# motherboard.net
KiCad netlist of a schematic drawn in EAGLE
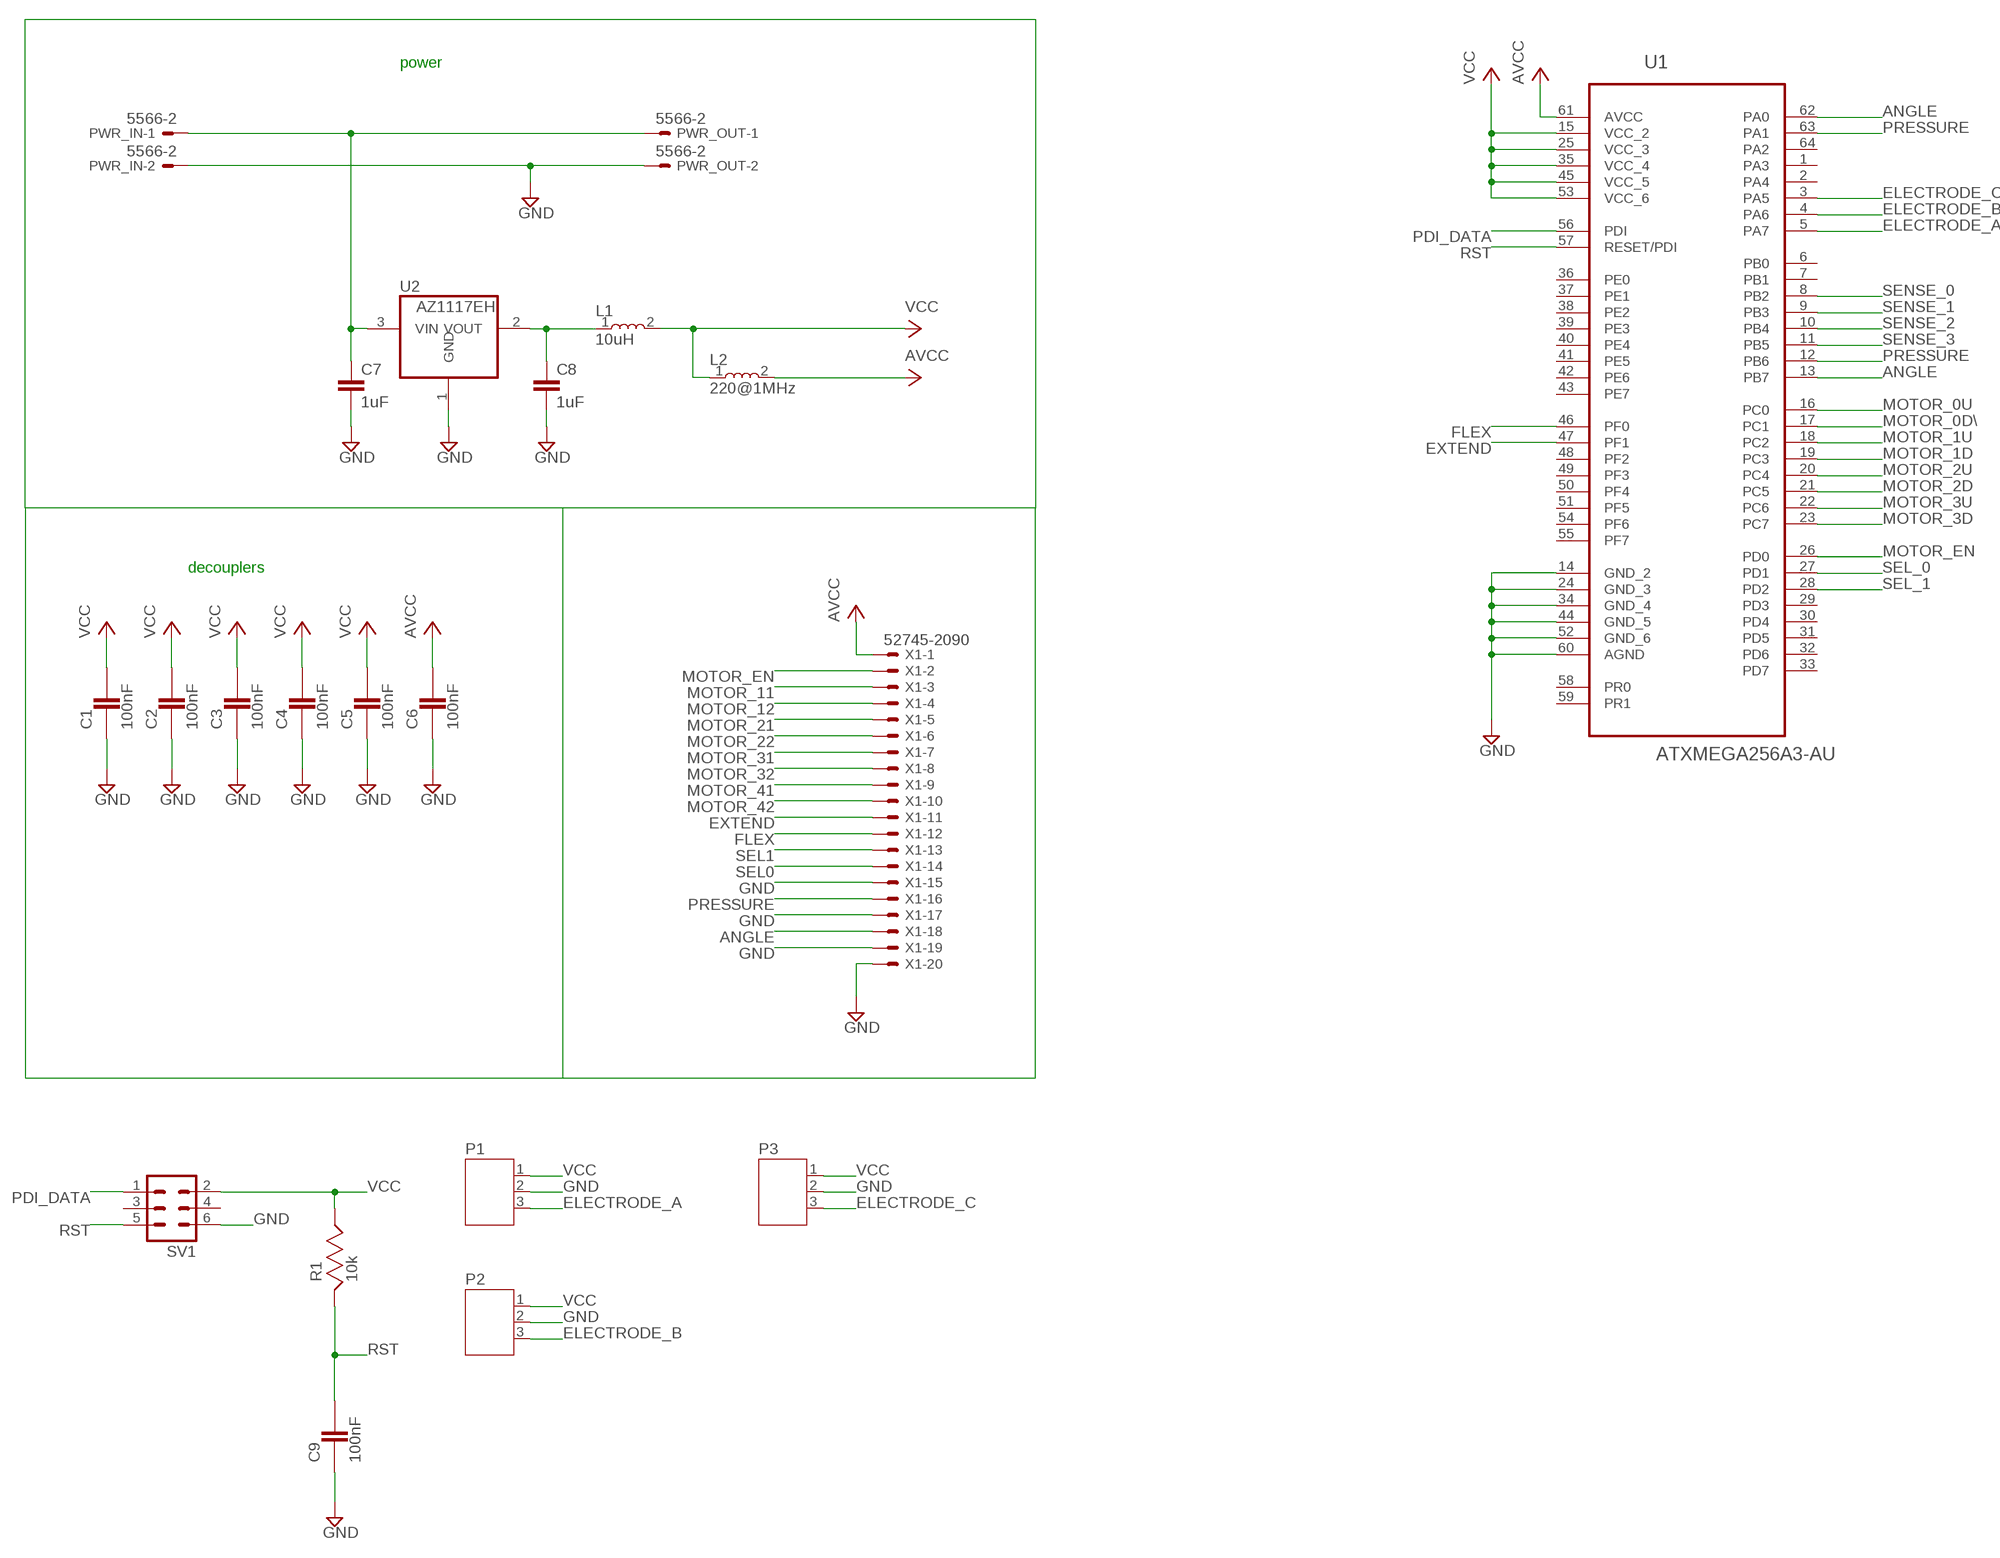
[diagram p0: schematic, sheet 1]

(export (version "E")
  (design (tool "Eeschema 10.0.6"))
  (components
    (comp (ref "C1")
      (value "100nF")
      (footprint "eagle-import:0508")
      (libsource (lib "eagle-import") (part "C0508"))
    )
    (comp (ref "C2")
      (value "100nF")
      (footprint "eagle-import:0508")
      (libsource (lib "eagle-import") (part "C0508"))
    )
    (comp (ref "C3")
      (value "100nF")
      (footprint "eagle-import:0508")
      (libsource (lib "eagle-import") (part "C0508"))
    )
    (comp (ref "C4")
      (value "100nF")
      (footprint "eagle-import:0508")
      (libsource (lib "eagle-import") (part "C0508"))
    )
    (comp (ref "C5")
      (value "100nF")
      (footprint "eagle-import:0508")
      (libsource (lib "eagle-import") (part "C0508"))
    )
    (comp (ref "C6")
      (value "100nF")
      (footprint "eagle-import:0508")
      (libsource (lib "eagle-import") (part "C0508"))
    )
    (comp (ref "C7")
      (value "1uF")
      (footprint "eagle-import:C0805")
      (libsource (lib "eagle-import") (part "C-EUC0805"))
    )
    (comp (ref "C8")
      (value "1uF")
      (footprint "eagle-import:C0805")
      (libsource (lib "eagle-import") (part "C-EUC0805"))
    )
    (comp (ref "C9")
      (value "100nF")
      (footprint "eagle-import:CC0603KRX7R8BB105_CAPC1608X90")
      (fields (field (name "MANUFACTURER") "YAGEO"))
      (libsource (lib "eagle-import") (part "CC0603KRX7R8BB105"))
    )
    (comp (ref "L1")
      (value "10uH")
      (footprint "eagle-import:0805")
      (libsource (lib "eagle-import") (part "L0805"))
    )
    (comp (ref "L2")
      (value "220@1MHz")
      (footprint "eagle-import:0805")
      (libsource (lib "eagle-import") (part "L0805"))
    )
    (comp (ref "P1")
      (value "JST-PH3")
      (footprint "eagle-import:JST-PH3")
      (libsource (lib "eagle-import") (part "JST-PH3"))
    )
    (comp (ref "P2")
      (value "JST-PH3")
      (footprint "eagle-import:JST-PH3")
      (libsource (lib "eagle-import") (part "JST-PH3"))
    )
    (comp (ref "P3")
      (value "JST-PH3")
      (footprint "eagle-import:JST-PH3")
      (libsource (lib "eagle-import") (part "JST-PH3"))
    )
    (comp (ref "PWR_IN")
      (value "5566-2")
      (footprint "eagle-import:5566-2")
      (libsource (lib "eagle-import") (part "5566-2"))
    )
    (comp (ref "PWR_OUT")
      (value "5566-2")
      (footprint "eagle-import:5566-2")
      (libsource (lib "eagle-import") (part "5566-2"))
    )
    (comp (ref "R1")
      (value "10k")
      (footprint "eagle-import:CRCW060310K0FKEA_RESC1608X55")
      (fields (field (name "MANUFACTURER") "VISHAY"))
      (libsource (lib "eagle-import") (part "CRCW060310K0FKEA"))
    )
    (comp (ref "SV1")
      (value "MA03-2")
      (footprint "eagle-import:MA03-2")
      (libsource (lib "eagle-import") (part "MA03-2"))
    )
    (comp (ref "U1")
      (value "ATXMEGA256A3-AU")
      (footprint "eagle-import:QFP80P1600X1600X120-64N")
      (fields (field (name "MF") "Atmel"))
      (libsource (lib "eagle-import") (part "ATXMEGA256A3-AU"))
    )
    (comp (ref "U2")
      (value "AZ1117EH")
      (footprint "eagle-import:SOT230P700X160-4N")
      (libsource (lib "eagle-import") (part "AZ1117EH"))
    )
    (comp (ref "X1")
      (value "52745-2090")
      (footprint "eagle-import:52745-2090")
      (fields (field (name "MF") "WALDOM/MOLEX"))
      (libsource (lib "eagle-import") (part "52745-2090"))
    )
  )
  (nets
    (net (code "1") (name "/ANGLE") (class "Default")
      (node (ref "U1") (pin "13") (pinfunction "PB7_13") (pintype "bidirectional"))
      (node (ref "U1") (pin "62") (pinfunction "PA0_62") (pintype "bidirectional"))
      (node (ref "X1") (pin "18") (pinfunction "S_18") (pintype "passive"))
    )
    (net (code "2") (name "/ELECTRODE_A") (class "Default")
      (node (ref "P1") (pin "3") (pinfunction "3_3") (pintype "passive"))
      (node (ref "U1") (pin "5") (pinfunction "PA7_5") (pintype "bidirectional"))
    )
    (net (code "3") (name "/ELECTRODE_B") (class "Default")
      (node (ref "P2") (pin "3") (pinfunction "3_3") (pintype "passive"))
      (node (ref "U1") (pin "4") (pinfunction "PA6_4") (pintype "bidirectional"))
    )
    (net (code "4") (name "/ELECTRODE_C") (class "Default")
      (node (ref "P3") (pin "3") (pinfunction "3_3") (pintype "passive"))
      (node (ref "U1") (pin "3") (pinfunction "PA5_3") (pintype "bidirectional"))
    )
    (net (code "5") (name "/EXTEND") (class "Default")
      (node (ref "U1") (pin "47") (pinfunction "PF1_47") (pintype "bidirectional"))
      (node (ref "X1") (pin "11") (pinfunction "S_11") (pintype "passive"))
    )
    (net (code "6") (name "/FLEX") (class "Default")
      (node (ref "U1") (pin "46") (pinfunction "PF0_46") (pintype "bidirectional"))
      (node (ref "X1") (pin "12") (pinfunction "S_12") (pintype "passive"))
    )
    (net (code "7") (name "/MOTOR_0D\\") (class "Default")
      (node (ref "U1") (pin "17") (pinfunction "PC1_17") (pintype "bidirectional"))
    )
    (net (code "8") (name "/MOTOR_0U") (class "Default")
      (node (ref "U1") (pin "16") (pinfunction "PC0_16") (pintype "bidirectional"))
    )
    (net (code "9") (name "/MOTOR_1D") (class "Default")
      (node (ref "U1") (pin "19") (pinfunction "PC3_19") (pintype "bidirectional"))
    )
    (net (code "10") (name "/MOTOR_1U") (class "Default")
      (node (ref "U1") (pin "18") (pinfunction "PC2_18") (pintype "bidirectional"))
    )
    (net (code "11") (name "/MOTOR_2D") (class "Default")
      (node (ref "U1") (pin "21") (pinfunction "PC5_21") (pintype "bidirectional"))
    )
    (net (code "12") (name "/MOTOR_2U") (class "Default")
      (node (ref "U1") (pin "20") (pinfunction "PC4_20") (pintype "bidirectional"))
    )
    (net (code "13") (name "/MOTOR_3D") (class "Default")
      (node (ref "U1") (pin "23") (pinfunction "PC7_23") (pintype "bidirectional"))
    )
    (net (code "14") (name "/MOTOR_3U") (class "Default")
      (node (ref "U1") (pin "22") (pinfunction "PC6_22") (pintype "bidirectional"))
    )
    (net (code "15") (name "/MOTOR_11") (class "Default")
      (node (ref "X1") (pin "3") (pinfunction "S_3") (pintype "passive"))
    )
    (net (code "16") (name "/MOTOR_12") (class "Default")
      (node (ref "X1") (pin "4") (pinfunction "S_4") (pintype "passive"))
    )
    (net (code "17") (name "/MOTOR_21") (class "Default")
      (node (ref "X1") (pin "5") (pinfunction "S_5") (pintype "passive"))
    )
    (net (code "18") (name "/MOTOR_22") (class "Default")
      (node (ref "X1") (pin "6") (pinfunction "S_6") (pintype "passive"))
    )
    (net (code "19") (name "/MOTOR_31") (class "Default")
      (node (ref "X1") (pin "7") (pinfunction "S_7") (pintype "passive"))
    )
    (net (code "20") (name "/MOTOR_32") (class "Default")
      (node (ref "X1") (pin "8") (pinfunction "S_8") (pintype "passive"))
    )
    (net (code "21") (name "/MOTOR_41") (class "Default")
      (node (ref "X1") (pin "9") (pinfunction "S_9") (pintype "passive"))
    )
    (net (code "22") (name "/MOTOR_42") (class "Default")
      (node (ref "X1") (pin "10") (pinfunction "S_10") (pintype "passive"))
    )
    (net (code "23") (name "/MOTOR_EN") (class "Default")
      (node (ref "U1") (pin "26") (pinfunction "PD0_26") (pintype "bidirectional"))
      (node (ref "X1") (pin "2") (pinfunction "S_2") (pintype "passive"))
    )
    (net (code "24") (name "/PDI_DATA") (class "Default")
      (node (ref "SV1") (pin "1") (pinfunction "1_1") (pintype "passive"))
      (node (ref "U1") (pin "56") (pinfunction "PDI_56") (pintype "input"))
    )
    (net (code "25") (name "/PRESSURE") (class "Default")
      (node (ref "U1") (pin "12") (pinfunction "PB6_12") (pintype "bidirectional"))
      (node (ref "U1") (pin "63") (pinfunction "PA1_63") (pintype "bidirectional"))
      (node (ref "X1") (pin "16") (pinfunction "S_16") (pintype "passive"))
    )
    (net (code "26") (name "/RST") (class "Default")
      (node (ref "C9") (pin "2") (pinfunction "2_2") (pintype "passive"))
      (node (ref "R1") (pin "1") (pinfunction "1_1") (pintype "passive"))
      (node (ref "SV1") (pin "5") (pinfunction "5_5") (pintype "passive"))
      (node (ref "U1") (pin "57") (pinfunction "RESET/PDI_57") (pintype "input"))
    )
    (net (code "27") (name "/SEL0") (class "Default")
      (node (ref "X1") (pin "14") (pinfunction "S_14") (pintype "passive"))
    )
    (net (code "28") (name "/SEL1") (class "Default")
      (node (ref "X1") (pin "13") (pinfunction "S_13") (pintype "passive"))
    )
    (net (code "29") (name "/SEL_0") (class "Default")
      (node (ref "U1") (pin "27") (pinfunction "PD1_27") (pintype "bidirectional"))
    )
    (net (code "30") (name "/SEL_1") (class "Default")
      (node (ref "U1") (pin "28") (pinfunction "PD2_28") (pintype "bidirectional"))
    )
    (net (code "31") (name "/SENSE_0") (class "Default")
      (node (ref "U1") (pin "8") (pinfunction "PB2_8") (pintype "bidirectional"))
    )
    (net (code "32") (name "/SENSE_1") (class "Default")
      (node (ref "U1") (pin "9") (pinfunction "PB3_9") (pintype "bidirectional"))
    )
    (net (code "33") (name "/SENSE_2") (class "Default")
      (node (ref "U1") (pin "10") (pinfunction "PB4_10") (pintype "bidirectional"))
    )
    (net (code "34") (name "/SENSE_3") (class "Default")
      (node (ref "U1") (pin "11") (pinfunction "PB5_11") (pintype "bidirectional"))
    )
    (net (code "35") (name "AVCC") (class "Default")
      (node (ref "C6") (pin "P$1") (pinfunction "1_P$1") (pintype "passive"))
      (node (ref "L2") (pin "2") (pinfunction "2_2") (pintype "passive"))
      (node (ref "U1") (pin "61") (pinfunction "AVCC_61") (pintype "power_in"))
      (node (ref "X1") (pin "1") (pinfunction "S_1") (pintype "passive"))
    )
    (net (code "36") (name "GND") (class "Default")
      (node (ref "C1") (pin "P$2") (pinfunction "2_P$2") (pintype "passive"))
      (node (ref "C2") (pin "P$2") (pinfunction "2_P$2") (pintype "passive"))
      (node (ref "C3") (pin "P$2") (pinfunction "2_P$2") (pintype "passive"))
      (node (ref "C4") (pin "P$2") (pinfunction "2_P$2") (pintype "passive"))
      (node (ref "C5") (pin "P$2") (pinfunction "2_P$2") (pintype "passive"))
      (node (ref "C6") (pin "P$2") (pinfunction "2_P$2") (pintype "passive"))
      (node (ref "C7") (pin "2") (pinfunction "2_2") (pintype "passive"))
      (node (ref "C8") (pin "2") (pinfunction "2_2") (pintype "passive"))
      (node (ref "C9") (pin "1") (pinfunction "1_1") (pintype "passive"))
      (node (ref "P1") (pin "2") (pinfunction "2_2") (pintype "passive"))
      (node (ref "P2") (pin "2") (pinfunction "2_2") (pintype "passive"))
      (node (ref "P3") (pin "2") (pinfunction "2_2") (pintype "passive"))
      (node (ref "PWR_IN") (pin "2") (pinfunction "S_2") (pintype "passive"))
      (node (ref "PWR_OUT") (pin "2") (pinfunction "S_2") (pintype "passive"))
      (node (ref "SV1") (pin "6") (pinfunction "6_6") (pintype "passive"))
      (node (ref "U1") (pin "14") (pinfunction "GND_2_14") (pintype "passive"))
      (node (ref "U1") (pin "24") (pinfunction "GND_3_24") (pintype "passive"))
      (node (ref "U1") (pin "34") (pinfunction "GND_4_34") (pintype "passive"))
      (node (ref "U1") (pin "44") (pinfunction "GND_5_44") (pintype "passive"))
      (node (ref "U1") (pin "52") (pinfunction "GND_6_52") (pintype "passive"))
      (node (ref "U1") (pin "60") (pinfunction "AGND_60") (pintype "passive"))
      (node (ref "U2") (pin "1") (pinfunction "GND_1") (pintype "power_in"))
      (node (ref "X1") (pin "15") (pinfunction "S_15") (pintype "passive"))
      (node (ref "X1") (pin "17") (pinfunction "S_17") (pintype "passive"))
      (node (ref "X1") (pin "19") (pinfunction "S_19") (pintype "passive"))
      (node (ref "X1") (pin "20") (pinfunction "S_20") (pintype "passive"))
    )
    (net (code "37") (name "Net-(PWR_INA-S)") (class "Default")
      (node (ref "C7") (pin "1") (pinfunction "1_1") (pintype "passive"))
      (node (ref "PWR_IN") (pin "1") (pinfunction "S_1") (pintype "passive"))
      (node (ref "PWR_OUT") (pin "1") (pinfunction "S_1") (pintype "passive"))
      (node (ref "U2") (pin "3") (pinfunction "VIN_3") (pintype "input"))
    )
    (net (code "38") (name "Net-(U2-VOUT)") (class "Default")
      (node (ref "C8") (pin "1") (pinfunction "1_1") (pintype "passive"))
      (node (ref "L1") (pin "1") (pinfunction "1_1") (pintype "passive"))
      (node (ref "U2") (pin "2") (pinfunction "VOUT_2") (pintype "output"))
    )
    (net (code "39") (name "VCC") (class "Default")
      (node (ref "C1") (pin "P$1") (pinfunction "1_P$1") (pintype "passive"))
      (node (ref "C2") (pin "P$1") (pinfunction "1_P$1") (pintype "passive"))
      (node (ref "C3") (pin "P$1") (pinfunction "1_P$1") (pintype "passive"))
      (node (ref "C4") (pin "P$1") (pinfunction "1_P$1") (pintype "passive"))
      (node (ref "C5") (pin "P$1") (pinfunction "1_P$1") (pintype "passive"))
      (node (ref "L1") (pin "2") (pinfunction "2_2") (pintype "passive"))
      (node (ref "L2") (pin "1") (pinfunction "1_1") (pintype "passive"))
      (node (ref "P1") (pin "1") (pinfunction "1_1") (pintype "passive"))
      (node (ref "P2") (pin "1") (pinfunction "1_1") (pintype "passive"))
      (node (ref "P3") (pin "1") (pinfunction "1_1") (pintype "passive"))
      (node (ref "R1") (pin "2") (pinfunction "2_2") (pintype "passive"))
      (node (ref "SV1") (pin "2") (pinfunction "2_2") (pintype "passive"))
      (node (ref "U1") (pin "15") (pinfunction "VCC_2_15") (pintype "power_in"))
      (node (ref "U1") (pin "25") (pinfunction "VCC_3_25") (pintype "power_in"))
      (node (ref "U1") (pin "35") (pinfunction "VCC_4_35") (pintype "power_in"))
      (node (ref "U1") (pin "45") (pinfunction "VCC_5_45") (pintype "power_in"))
      (node (ref "U1") (pin "53") (pinfunction "VCC_6_53") (pintype "power_in"))
    )
    (net (code "40") (name "unconnected-(SV1-Pad3)") (class "Default")
      (node (ref "SV1") (pin "3") (pinfunction "3_3") (pintype "passive"))
    )
    (net (code "41") (name "unconnected-(SV1-Pad4)") (class "Default")
      (node (ref "SV1") (pin "4") (pinfunction "4_4") (pintype "passive"))
    )
    (net (code "42") (name "unconnected-(U1-PA2-Pad64)") (class "Default")
      (node (ref "U1") (pin "64") (pinfunction "PA2_64") (pintype "bidirectional"))
    )
    (net (code "43") (name "unconnected-(U1-PA3-Pad1)") (class "Default")
      (node (ref "U1") (pin "1") (pinfunction "PA3_1") (pintype "bidirectional"))
    )
    (net (code "44") (name "unconnected-(U1-PA4-Pad2)") (class "Default")
      (node (ref "U1") (pin "2") (pinfunction "PA4_2") (pintype "bidirectional"))
    )
    (net (code "45") (name "unconnected-(U1-PB0-Pad6)") (class "Default")
      (node (ref "U1") (pin "6") (pinfunction "PB0_6") (pintype "bidirectional"))
    )
    (net (code "46") (name "unconnected-(U1-PB1-Pad7)") (class "Default")
      (node (ref "U1") (pin "7") (pinfunction "PB1_7") (pintype "bidirectional"))
    )
    (net (code "47") (name "unconnected-(U1-PD3-Pad29)") (class "Default")
      (node (ref "U1") (pin "29") (pinfunction "PD3_29") (pintype "bidirectional"))
    )
    (net (code "48") (name "unconnected-(U1-PD4-Pad30)") (class "Default")
      (node (ref "U1") (pin "30") (pinfunction "PD4_30") (pintype "bidirectional"))
    )
    (net (code "49") (name "unconnected-(U1-PD5-Pad31)") (class "Default")
      (node (ref "U1") (pin "31") (pinfunction "PD5_31") (pintype "bidirectional"))
    )
    (net (code "50") (name "unconnected-(U1-PD6-Pad32)") (class "Default")
      (node (ref "U1") (pin "32") (pinfunction "PD6_32") (pintype "bidirectional"))
    )
    (net (code "51") (name "unconnected-(U1-PD7-Pad33)") (class "Default")
      (node (ref "U1") (pin "33") (pinfunction "PD7_33") (pintype "bidirectional"))
    )
    (net (code "52") (name "unconnected-(U1-PE0-Pad36)") (class "Default")
      (node (ref "U1") (pin "36") (pinfunction "PE0_36") (pintype "bidirectional"))
    )
    (net (code "53") (name "unconnected-(U1-PE1-Pad37)") (class "Default")
      (node (ref "U1") (pin "37") (pinfunction "PE1_37") (pintype "bidirectional"))
    )
    (net (code "54") (name "unconnected-(U1-PE2-Pad38)") (class "Default")
      (node (ref "U1") (pin "38") (pinfunction "PE2_38") (pintype "bidirectional"))
    )
    (net (code "55") (name "unconnected-(U1-PE3-Pad39)") (class "Default")
      (node (ref "U1") (pin "39") (pinfunction "PE3_39") (pintype "bidirectional"))
    )
    (net (code "56") (name "unconnected-(U1-PE4-Pad40)") (class "Default")
      (node (ref "U1") (pin "40") (pinfunction "PE4_40") (pintype "bidirectional"))
    )
    (net (code "57") (name "unconnected-(U1-PE5-Pad41)") (class "Default")
      (node (ref "U1") (pin "41") (pinfunction "PE5_41") (pintype "bidirectional"))
    )
    (net (code "58") (name "unconnected-(U1-PE6-Pad42)") (class "Default")
      (node (ref "U1") (pin "42") (pinfunction "PE6_42") (pintype "bidirectional"))
    )
    (net (code "59") (name "unconnected-(U1-PE7-Pad43)") (class "Default")
      (node (ref "U1") (pin "43") (pinfunction "PE7_43") (pintype "bidirectional"))
    )
    (net (code "60") (name "unconnected-(U1-PF2-Pad48)") (class "Default")
      (node (ref "U1") (pin "48") (pinfunction "PF2_48") (pintype "bidirectional"))
    )
    (net (code "61") (name "unconnected-(U1-PF3-Pad49)") (class "Default")
      (node (ref "U1") (pin "49") (pinfunction "PF3_49") (pintype "bidirectional"))
    )
    (net (code "62") (name "unconnected-(U1-PF4-Pad50)") (class "Default")
      (node (ref "U1") (pin "50") (pinfunction "PF4_50") (pintype "bidirectional"))
    )
    (net (code "63") (name "unconnected-(U1-PF5-Pad51)") (class "Default")
      (node (ref "U1") (pin "51") (pinfunction "PF5_51") (pintype "bidirectional"))
    )
    (net (code "64") (name "unconnected-(U1-PF6-Pad54)") (class "Default")
      (node (ref "U1") (pin "54") (pinfunction "PF6_54") (pintype "bidirectional"))
    )
    (net (code "65") (name "unconnected-(U1-PF7-Pad55)") (class "Default")
      (node (ref "U1") (pin "55") (pinfunction "PF7_55") (pintype "bidirectional"))
    )
    (net (code "66") (name "unconnected-(U1-PR0-Pad58)") (class "Default")
      (node (ref "U1") (pin "58") (pinfunction "PR0_58") (pintype "input"))
    )
    (net (code "67") (name "unconnected-(U1-PR1-Pad59)") (class "Default")
      (node (ref "U1") (pin "59") (pinfunction "PR1_59") (pintype "input"))
    )
  )
)
